# OLED_Display.net
KiCad netlist of a schematic drawn in Altium Designer
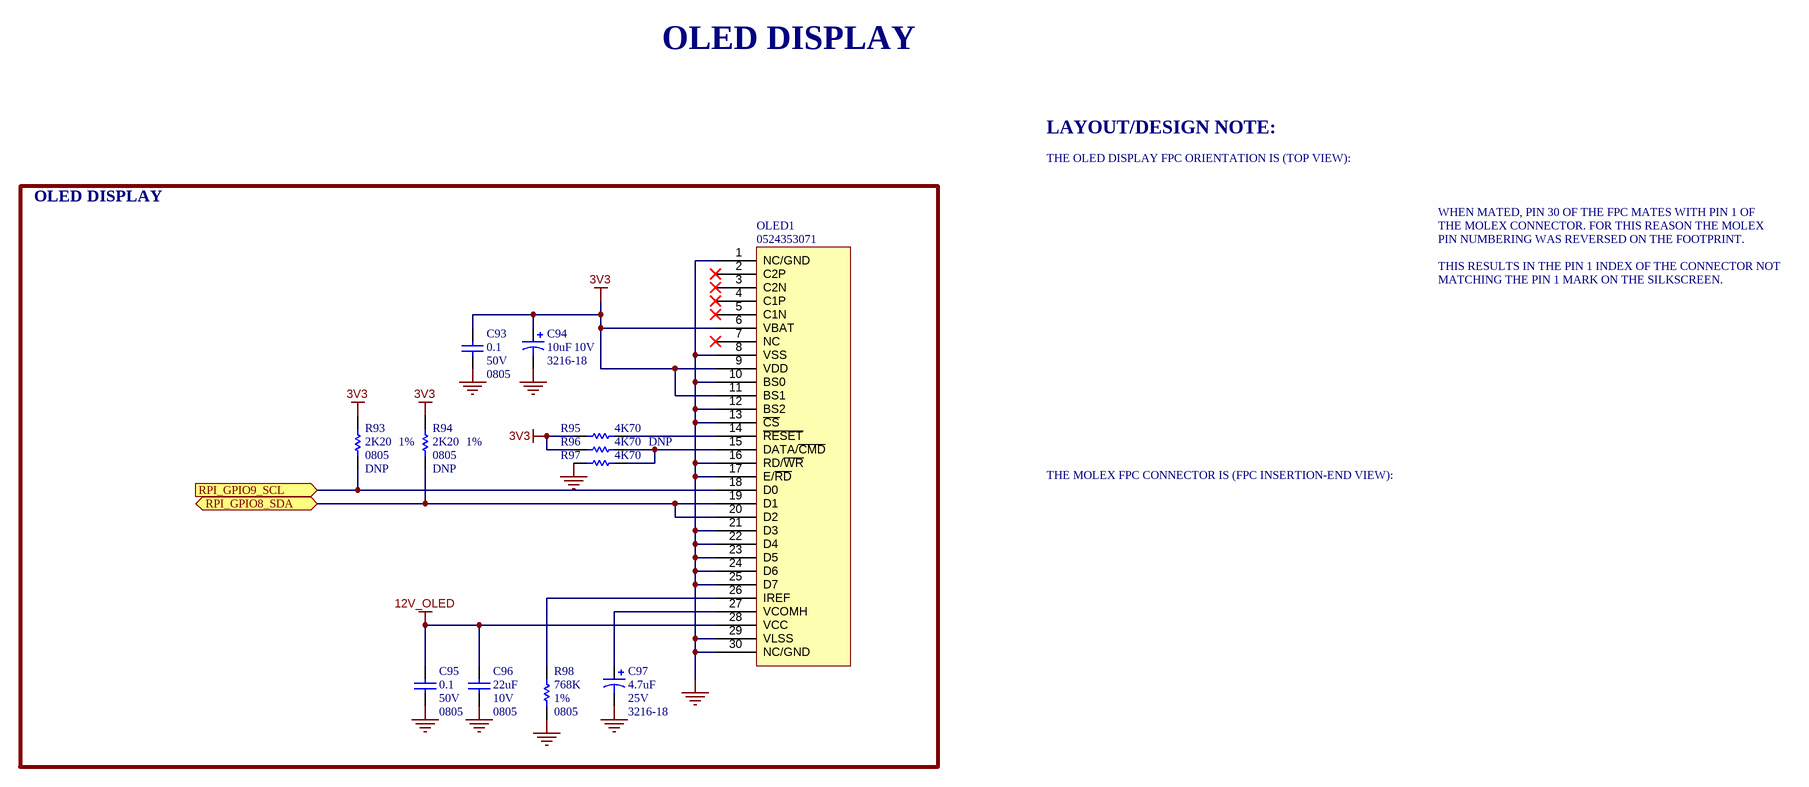
[diagram p0: OLED Display.SchDoc]

(export (version "E")
  (design (tool "Eeschema 10.0.6"))
  (components
    (comp (ref "C93")
      (value "0.1")
      (footprint "C0805")
      (description "Capacitor")
      (fields
        (field (name "TOLERANCE") "10%")
        (field (name "VOLTAGE") "50V")
        (field (name "PACKAGE") "0805")
        (field (name "MFG") "Yageo")
      )
      (libsource (lib "CPR_CommonDevices") (part "Capacitor _SMT"))
    )
    (comp (ref "C94")
      (value "10uF")
      (footprint "CAP_TANT_3216-18")
      (description "Polarized Capacitor (Radial)")
      (fields
        (field (name "VOLTAGE") "10V")
        (field (name "TOLERANCE") "10%")
        (field (name "MFG") "Kemet")
        (field (name "PACKAGE") "3216-18")
      )
      (libsource (lib "Miscellaneous Devices") (part "Cap Pol1"))
    )
    (comp (ref "C95")
      (value "0.1")
      (footprint "C0805")
      (description "Capacitor")
      (fields
        (field (name "TOLERANCE") "10%")
        (field (name "VOLTAGE") "50V")
        (field (name "PACKAGE") "0805")
        (field (name "MFG") "Yageo")
      )
      (libsource (lib "CPR_CommonDevices") (part "Capacitor _SMT"))
    )
    (comp (ref "C96")
      (value "22uF")
      (footprint "C0805")
      (description "Capacitor")
      (fields
        (field (name "TOLERANCE") "-20 +80")
        (field (name "VOLTAGE") "10V")
        (field (name "PACKAGE") "0805")
        (field (name "MFG") "Yageo")
      )
      (libsource (lib "CPR_CommonDevices") (part "Capacitor _SMT"))
    )
    (comp (ref "C97")
      (value "4.7uF")
      (footprint "CAP_TANT_3216-18")
      (description "Polarized Capacitor (Radial)")
      (fields
        (field (name "VOLTAGE") "25V")
        (field (name "TOLERANCE") "10%")
        (field (name "MFG") "Kemet")
        (field (name "PACKAGE") "3216-18")
      )
      (libsource (lib "Miscellaneous Devices") (part "Cap Pol1"))
    )
    (comp (ref "OLED1")
      (value "128x64 OLED")
      (footprint "MOLEX_0524353071_REV")
      (description "128x64 OLED module")
      (fields (field (name "MANUFACTURER") "Molex") (field (name "MFG PN") "0524353071"))
      (libsource (lib "ER-OLED013-1") (part "ER-OLED013-1"))
    )
    (comp (ref "R93")
      (value "2K20")
      (footprint "R0805")
      (description "Resistor")
      (fields
        (field (name "TOLERANCE") "1%")
        (field (name "DNP") "DNP")
        (field (name "PACKAGE") "0805")
        (field (name "MFG") "Yageo")
        (field (name "Comment") "Resistor_SMT")
      )
      (libsource (lib "CPR_CommonDevices") (part "Resistor_SMT"))
    )
    (comp (ref "R94")
      (value "2K20")
      (footprint "R0805")
      (description "Resistor")
      (fields
        (field (name "TOLERANCE") "1%")
        (field (name "DNP") "DNP")
        (field (name "PACKAGE") "0805")
        (field (name "MFG") "Yageo")
        (field (name "Comment") "Resistor_SMT")
      )
      (libsource (lib "CPR_CommonDevices") (part "Resistor_SMT"))
    )
    (comp (ref "R95")
      (value "4K70")
      (footprint "R0805")
      (description "Resistor")
      (fields (field (name "TOLERANCE") "1%") (field (name "MFG") "Yageo"))
      (libsource (lib "CPR_CommonDevices") (part "Resistor_SMT"))
    )
    (comp (ref "R96")
      (value "4K70")
      (footprint "R0805")
      (description "Resistor")
      (fields (field (name "TOLERANCE") "1%") (field (name "DNP") "DNP") (field (name "MFG") "Yageo"))
      (libsource (lib "CPR_CommonDevices") (part "Resistor_SMT"))
    )
    (comp (ref "R97")
      (value "4K70")
      (footprint "R0805")
      (description "Resistor")
      (fields (field (name "TOLERANCE") "1%") (field (name "MFG") "Yageo"))
      (libsource (lib "CPR_CommonDevices") (part "Resistor_SMT"))
    )
    (comp (ref "R98")
      (value "768K")
      (footprint "R0805")
      (description "Resistor")
      (fields
        (field (name "TOLERANCE") "1%")
        (field (name "PACKAGE") "0805")
        (field (name "MFG") "Yageo")
        (field (name "Comment") "Resistor_SMT")
      )
      (libsource (lib "CPR_CommonDevices") (part "Resistor_SMT"))
    )
  )
  (nets
    (net (code "1") (name "/RPI_GPIO8_SDA") (class "Default")
      (node (ref "OLED1") (pin "19") (pinfunction "D1_19") (pintype "passive"))
      (node (ref "OLED1") (pin "20") (pinfunction "D2_20") (pintype "passive"))
      (node (ref "R94") (pin "2") (pinfunction "2_2") (pintype "passive"))
    )
    (net (code "2") (name "/RPI_GPIO9_SCL") (class "Default")
      (node (ref "OLED1") (pin "18") (pinfunction "D0_18") (pintype "passive"))
      (node (ref "R93") (pin "2") (pinfunction "2_2") (pintype "passive"))
    )
    (net (code "3") (name "3V3") (class "Default")
      (node (ref "C93") (pin "2") (pinfunction "2_2") (pintype "passive"))
      (node (ref "C94") (pin "1") (pinfunction "1_1") (pintype "passive"))
      (node (ref "OLED1") (pin "11") (pinfunction "BS1_11") (pintype "passive"))
      (node (ref "OLED1") (pin "6") (pinfunction "VBAT_6") (pintype "passive"))
      (node (ref "OLED1") (pin "9") (pinfunction "VDD_9") (pintype "passive"))
      (node (ref "R93") (pin "1") (pinfunction "1_1") (pintype "passive"))
      (node (ref "R94") (pin "1") (pinfunction "1_1") (pintype "passive"))
      (node (ref "R95") (pin "2") (pinfunction "2_2") (pintype "passive"))
      (node (ref "R96") (pin "2") (pinfunction "2_2") (pintype "passive"))
    )
    (net (code "4") (name "12V_OLED") (class "Default")
      (node (ref "C95") (pin "2") (pinfunction "2_2") (pintype "passive"))
      (node (ref "C96") (pin "2") (pinfunction "2_2") (pintype "passive"))
      (node (ref "OLED1") (pin "28") (pinfunction "VCC_28") (pintype "passive"))
    )
    (net (code "5") (name "GND") (class "Default")
      (node (ref "C93") (pin "1") (pinfunction "1_1") (pintype "passive"))
      (node (ref "C94") (pin "2") (pinfunction "2_2") (pintype "passive"))
      (node (ref "C95") (pin "1") (pinfunction "1_1") (pintype "passive"))
      (node (ref "C96") (pin "1") (pinfunction "1_1") (pintype "passive"))
      (node (ref "C97") (pin "2") (pinfunction "2_2") (pintype "passive"))
      (node (ref "OLED1") (pin "1") (pinfunction "NC/GND_1") (pintype "passive"))
      (node (ref "OLED1") (pin "10") (pinfunction "BS0_10") (pintype "passive"))
      (node (ref "OLED1") (pin "12") (pinfunction "BS2_12") (pintype "passive"))
      (node (ref "OLED1") (pin "13") (pinfunction "~{CS}_13") (pintype "passive"))
      (node (ref "OLED1") (pin "16") (pinfunction "RD/~{WR}_16") (pintype "passive"))
      (node (ref "OLED1") (pin "17") (pinfunction "E/~{RD}_17") (pintype "passive"))
      (node (ref "OLED1") (pin "21") (pinfunction "D3_21") (pintype "passive"))
      (node (ref "OLED1") (pin "22") (pinfunction "D4_22") (pintype "passive"))
      (node (ref "OLED1") (pin "23") (pinfunction "D5_23") (pintype "passive"))
      (node (ref "OLED1") (pin "24") (pinfunction "D6_24") (pintype "passive"))
      (node (ref "OLED1") (pin "25") (pinfunction "D7_25") (pintype "passive"))
      (node (ref "OLED1") (pin "29") (pinfunction "VLSS_29") (pintype "passive"))
      (node (ref "OLED1") (pin "30") (pinfunction "NC/GND_30") (pintype "passive"))
      (node (ref "OLED1") (pin "8") (pinfunction "VSS_8") (pintype "passive"))
      (node (ref "R97") (pin "2") (pinfunction "2_2") (pintype "passive"))
      (node (ref "R98") (pin "2") (pinfunction "2_2") (pintype "passive"))
    )
    (net (code "6") (name "Net-(OLED1-DATA{slash}~{CMD})") (class "Default")
      (node (ref "OLED1") (pin "15") (pinfunction "DATA/~{CMD}_15") (pintype "passive"))
      (node (ref "R96") (pin "1") (pinfunction "1_1") (pintype "passive"))
      (node (ref "R97") (pin "1") (pinfunction "1_1") (pintype "passive"))
    )
    (net (code "7") (name "Net-(OLED1-IREF)") (class "Default")
      (node (ref "OLED1") (pin "26") (pinfunction "IREF_26") (pintype "passive"))
      (node (ref "R98") (pin "1") (pinfunction "1_1") (pintype "passive"))
    )
    (net (code "8") (name "Net-(OLED1-VCOMH)") (class "Default")
      (node (ref "C97") (pin "1") (pinfunction "1_1") (pintype "passive"))
      (node (ref "OLED1") (pin "27") (pinfunction "VCOMH_27") (pintype "passive"))
    )
    (net (code "9") (name "Net-(OLED1-~{RESET})") (class "Default")
      (node (ref "OLED1") (pin "14") (pinfunction "~{RESET}_14") (pintype "passive"))
      (node (ref "R95") (pin "1") (pinfunction "1_1") (pintype "passive"))
    )
    (net (code "10") (name "unconnected-(OLED1-C1N-Pad5)") (class "Default")
      (node (ref "OLED1") (pin "5") (pinfunction "C1N_5") (pintype "passive+no_connect"))
    )
    (net (code "11") (name "unconnected-(OLED1-C1P-Pad4)") (class "Default")
      (node (ref "OLED1") (pin "4") (pinfunction "C1P_4") (pintype "passive+no_connect"))
    )
    (net (code "12") (name "unconnected-(OLED1-C2N-Pad3)") (class "Default")
      (node (ref "OLED1") (pin "3") (pinfunction "C2N_3") (pintype "passive+no_connect"))
    )
    (net (code "13") (name "unconnected-(OLED1-C2P-Pad2)") (class "Default")
      (node (ref "OLED1") (pin "2") (pinfunction "C2P_2") (pintype "passive+no_connect"))
    )
    (net (code "14") (name "unconnected-(OLED1-NC-Pad7)") (class "Default")
      (node (ref "OLED1") (pin "7") (pinfunction "NC_7") (pintype "passive+no_connect"))
    )
  )
)
